# Sheet3_2_AMP.net
KiCad netlist of a schematic drawn in Altium Designer
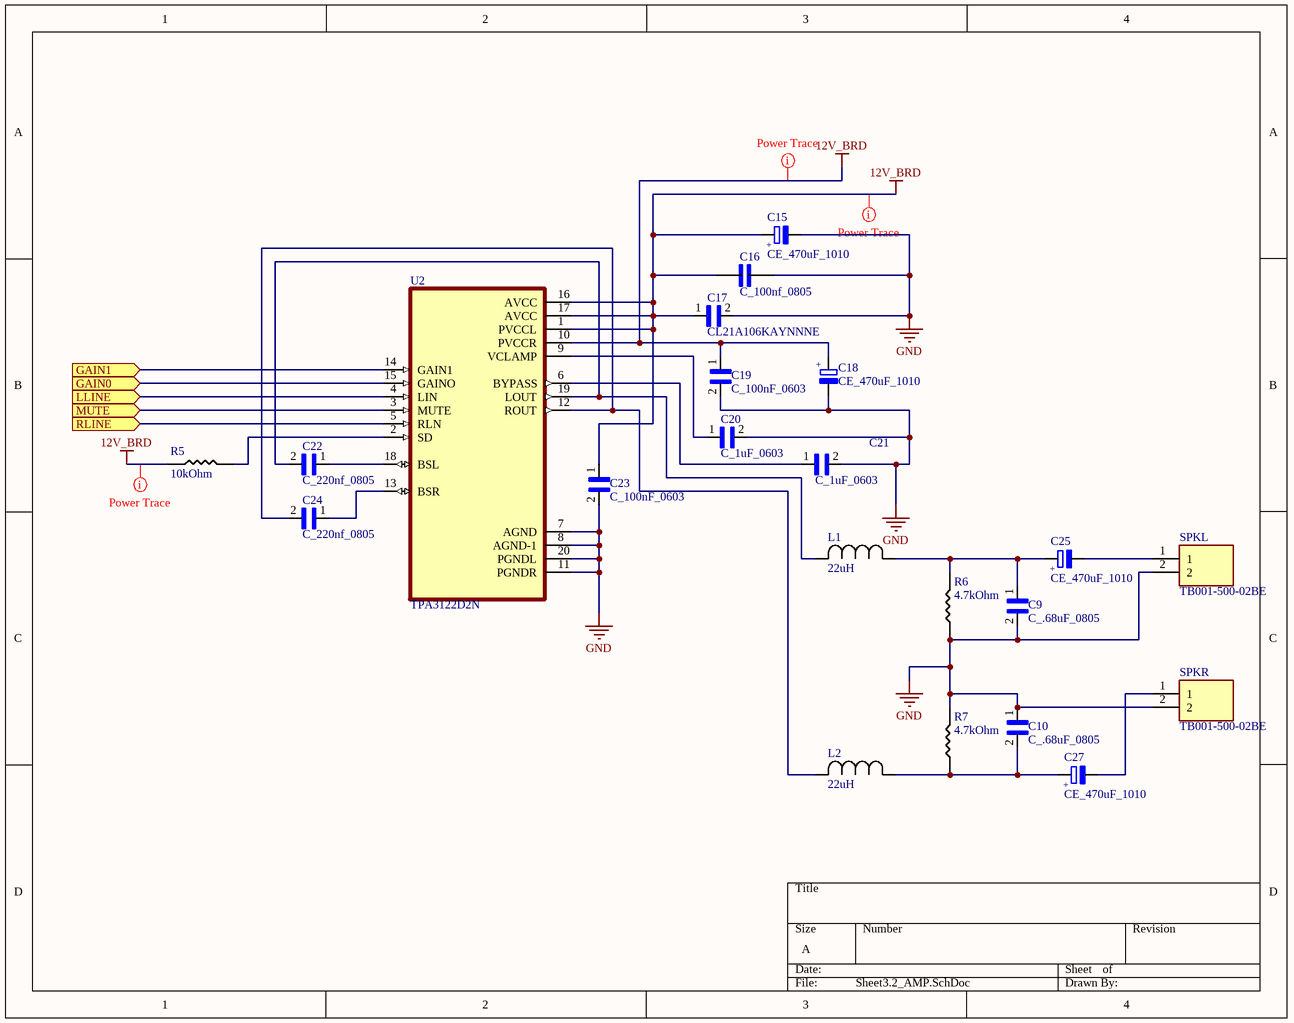
[diagram p0: Sheet3.2_AMP.SchDoc]

(export (version "E")
  (design (tool "Eeschema 10.0.6"))
  (components
    (comp (ref "C9")
      (value "C_.68uF_0805")
      (footprint "CAPC2012X140N")
      (description ".68µF 0805 ±20% 25V Ceramic Capacitor X5R 0805 (2012 Metric)")
      (fields (field (name "MF") "Samsung") (field (name "MP") "CL21B684KOFNNNE"))
      (libsource (lib "Homie_IntegratedLibraryV2") (part "C_.68uF_0805"))
    )
    (comp (ref "C10")
      (value "C_.68uF_0805")
      (footprint "CAPC2012X140N")
      (description ".68µF 0805 ±20% 25V Ceramic Capacitor X5R 0805 (2012 Metric)")
      (fields (field (name "MF") "Samsung") (field (name "MP") "CL21B684KOFNNNE"))
      (libsource (lib "Homie_IntegratedLibraryV2") (part "C_.68uF_0805"))
    )
    (comp (ref "C15")
      (value "CE_470uF_1010")
      (footprint "140CLH-1010")
      (description "Aluminum Electrolytic Capacitors - SMD")
      (fields (field (name "MP") "VZH471M1ETR-1010") (field (name "MF") "Lelon"))
      (libsource (lib "Homie_IntegratedLibraryV2") (part "CE_470uF_1010"))
    )
    (comp (ref "C16")
      (value "C_100nf_0805")
      (footprint "CAPC2012X70")
      (description "0.1ÂµF Â±10% 50V Ceramic Capacitor X7R 0805 _2012 Metric_  CC0805KRX7R9BB104")
      (fields (field (name "MF") "Yageo") (field (name "MP") "CC0805KRX7R9BB104"))
      (libsource (lib "Homie_IntegratedLibraryV2") (part "C_100nf_0805"))
    )
    (comp (ref "C17")
      (value "CL21A106KAYNNNE")
      (footprint "CAPC2012X135N")
      (description "10ÂµF Â±10% 25V Ceramic Capacitor X5R 0805 (2012 Metric)CL21A106KAYNNNE")
      (fields (field (name "MF") "Samsung"))
      (libsource (lib "Homie_IntegratedLibraryV2") (part "CL21A106KAYNNNE"))
    )
    (comp (ref "C18")
      (value "CE_470uF_1010")
      (footprint "140CLH-1010")
      (description "Aluminum Electrolytic Capacitors - SMD")
      (fields (field (name "MP") "VZH471M1ETR-1010") (field (name "MF") "Lelon"))
      (libsource (lib "") (part "CE_470uF_1010_1"))
    )
    (comp (ref "C19")
      (value "C_100nF_0603")
      (footprint "CAPC1608X90")
      (description "0.1礔/100nF  卤10% 50V Ceramic Capacitor X7R 0603 _1608 Metric_")
      (fields (field (name "DIGI-KEY_PART_NUMBER") "311-1344-1-ND") (field (name "MP") "CC0603KRX7R9BB104"))
      (libsource (lib "Homie_IntegratedLibraryV2") (part "C_100nF_0603"))
    )
    (comp (ref "C20")
      (value "C_1uF_0603")
      (footprint "CAPC1608X90N")
      (description "1uF ±10% 50V Ceramic Capacitor X7R 0603 (1608 Metric)")
      (fields (field (name "MP") "CL10A105KB8NNNC") (field (name "MF") "Samsung"))
      (libsource (lib "Homie_IntegratedLibraryV2") (part "C_1uF_0603"))
    )
    (comp (ref "C21")
      (value "C_1uF_0603")
      (footprint "CAPC1608X90N")
      (description "1uF ±10% 50V Ceramic Capacitor X7R 0603 (1608 Metric)")
      (fields (field (name "MP") "CL10A105KB8NNNC") (field (name "MF") "Samsung"))
      (libsource (lib "Homie_IntegratedLibraryV2") (part "C_1uF_0603"))
    )
    (comp (ref "C22")
      (value "C_220nf_0805")
      (footprint "CAPC2012X135N")
      (description "CL21B224KBFNNNE")
      (libsource (lib "Homie_IntegratedLibraryV2") (part "C_220nf_0805"))
    )
    (comp (ref "C23")
      (value "C_100nF_0603")
      (footprint "CAPC1608X90")
      (description "0.1礔/100nF  卤10% 50V Ceramic Capacitor X7R 0603 _1608 Metric_")
      (fields (field (name "DIGI-KEY_PART_NUMBER") "311-1344-1-ND") (field (name "MP") "CC0603KRX7R9BB104"))
      (libsource (lib "Homie_IntegratedLibraryV2") (part "C_100nF_0603"))
    )
    (comp (ref "C24")
      (value "C_220nf_0805")
      (footprint "CAPC2012X135N")
      (description "CL21B224KBFNNNE")
      (libsource (lib "Homie_IntegratedLibraryV2") (part "C_220nf_0805"))
    )
    (comp (ref "C25")
      (value "CE_470uF_1010")
      (footprint "140CLH-1010")
      (description "Aluminum Electrolytic Capacitors - SMD")
      (fields (field (name "MP") "VZH471M1ETR-1010") (field (name "MF") "Lelon"))
      (libsource (lib "Homie_IntegratedLibraryV2") (part "CE_470uF_1010"))
    )
    (comp (ref "C27")
      (value "CE_470uF_1010")
      (footprint "140CLH-1010")
      (description "Aluminum Electrolytic Capacitors - SMD")
      (fields (field (name "MP") "VZH471M1ETR-1010") (field (name "MF") "Lelon"))
      (libsource (lib "Homie_IntegratedLibraryV2") (part "CE_470uF_1010"))
    )
    (comp (ref "L1")
      (value "22uH")
      (footprint "L0805")
      (description "22uH SDFL2012T220KTF")
      (fields (field (name "MANUFACTURER_PART_NUMBER") "SDFL2012T220KTF"))
      (libsource (lib "Homie_IntegratedLibraryV2") (part "L_22uH"))
    )
    (comp (ref "L2")
      (value "22uH")
      (footprint "L0805")
      (description "22uH SDFL2012T220KTF")
      (fields (field (name "MANUFACTURER_PART_NUMBER") "SDFL2012T220KTF"))
      (libsource (lib "Homie_IntegratedLibraryV2") (part "L_22uH"))
    )
    (comp (ref "R5")
      (value "10kOhm")
      (footprint "R0805")
      (description "10kOhm +-1%  0805")
      (fields (field (name "MFR") "Uniroyal") (field (name "Comment") "10 kOhm"))
      (libsource (lib "Homie_IntegratedLibraryV2") (part "R_10kOhm_0805"))
    )
    (comp (ref "R6")
      (value "4.7kOhm")
      (footprint "R0805")
      (description "4.7kOhm +-1%  0805")
      (fields (field (name "MFR") "Uniroyal"))
      (libsource (lib "Homie_IntegratedLibraryV2") (part "R_4.7kOhm_0805"))
    )
    (comp (ref "R7")
      (value "4.7kOhm")
      (footprint "R0805")
      (description "4.7kOhm +-1%  0805")
      (fields (field (name "MFR") "Uniroyal"))
      (libsource (lib "Homie_IntegratedLibraryV2") (part "R_4.7kOhm_0805"))
    )
    (comp (ref "SPKL")
      (value "TB001-500-02BE")
      (footprint "CUI_TB001-500-02BE")
      (description "2~24 Poles, Screw Type, Horizontal, 5.0 Pitch, 22~12 _AWG_, Terminal Block Connector")
      (fields (field (name "MF") "CUI Devices"))
      (libsource (lib "Homie_IntegratedLibraryV3") (part "TB001-500-02BE"))
    )
    (comp (ref "SPKR")
      (value "TB001-500-02BE")
      (footprint "CUI_TB001-500-02BE")
      (description "2~24 Poles, Screw Type, Horizontal, 5.0 Pitch, 22~12 _AWG_, Terminal Block Connector")
      (fields (field (name "MF") "CUI Devices"))
      (libsource (lib "Homie_IntegratedLibraryV3") (part "TB001-500-02BE"))
    )
    (comp (ref "U2")
      (value "TPA3122D2N")
      (footprint "DIP20-2.54-26.2X7.62MM")
      (fields (field (name "MF") "Texas Instruments"))
      (libsource (lib "Homie_IntegratedLibraryV2") (part "TPA3122D2N"))
    )
  )
  (nets
    (net (code "1") (name "/GAIN0") (class "Default")
      (node (ref "U2") (pin "15") (pinfunction "GAINO_15") (pintype "input"))
    )
    (net (code "2") (name "/GAIN1") (class "Default")
      (node (ref "U2") (pin "14") (pinfunction "GAIN1_14") (pintype "input"))
    )
    (net (code "3") (name "/LLINE") (class "Default")
      (node (ref "U2") (pin "4") (pinfunction "LIN_4") (pintype "input"))
    )
    (net (code "4") (name "/MUTE") (class "Default")
      (node (ref "U2") (pin "3") (pinfunction "MUTE_3") (pintype "input"))
    )
    (net (code "5") (name "/RLINE") (class "Default")
      (node (ref "U2") (pin "5") (pinfunction "RLN_5") (pintype "input"))
    )
    (net (code "6") (name "12V_BRD") (class "Default")
      (node (ref "C15") (pin "POS") (pinfunction "POS_POS") (pintype "passive"))
      (node (ref "C16") (pin "1") (pinfunction "1_1") (pintype "passive"))
      (node (ref "C17") (pin "1") (pinfunction "1_1") (pintype "passive"))
      (node (ref "C18") (pin "POS") (pinfunction "POS_POS") (pintype "passive"))
      (node (ref "C19") (pin "1") (pinfunction "1_1") (pintype "passive"))
      (node (ref "C23") (pin "1") (pinfunction "1_1") (pintype "passive"))
      (node (ref "R5") (pin "1") (pinfunction "1_1") (pintype "passive"))
      (node (ref "U2") (pin "1") (pinfunction "PVCCL_1") (pintype "power_in"))
      (node (ref "U2") (pin "10") (pinfunction "PVCCR_10") (pintype "power_in"))
      (node (ref "U2") (pin "16") (pinfunction "AVCC_16") (pintype "power_in"))
      (node (ref "U2") (pin "17") (pinfunction "AVCC_17") (pintype "power_in"))
    )
    (net (code "7") (name "GND") (class "Default")
      (node (ref "C10") (pin "1") (pinfunction "1_1") (pintype "passive"))
      (node (ref "C15") (pin "NEG") (pinfunction "NEG_NEG") (pintype "passive"))
      (node (ref "C16") (pin "2") (pinfunction "2_2") (pintype "passive"))
      (node (ref "C17") (pin "2") (pinfunction "2_2") (pintype "passive"))
      (node (ref "C18") (pin "NEG") (pinfunction "NEG_NEG") (pintype "passive"))
      (node (ref "C19") (pin "2") (pinfunction "2_2") (pintype "passive"))
      (node (ref "C20") (pin "2") (pinfunction "2_2") (pintype "passive"))
      (node (ref "C21") (pin "2") (pinfunction "2_2") (pintype "passive"))
      (node (ref "C23") (pin "2") (pinfunction "2_2") (pintype "passive"))
      (node (ref "C9") (pin "2") (pinfunction "2_2") (pintype "passive"))
      (node (ref "R6") (pin "1") (pinfunction "1_1") (pintype "passive"))
      (node (ref "R7") (pin "2") (pinfunction "2_2") (pintype "passive"))
      (node (ref "SPKL") (pin "2") (pinfunction "2_2") (pintype "passive"))
      (node (ref "SPKR") (pin "2") (pinfunction "2_2") (pintype "passive"))
      (node (ref "U2") (pin "11") (pinfunction "PGNDR_11") (pintype "power_in"))
      (node (ref "U2") (pin "20") (pinfunction "PGNDL_20") (pintype "power_in"))
      (node (ref "U2") (pin "7") (pinfunction "AGND_7") (pintype "power_in"))
      (node (ref "U2") (pin "8") (pinfunction "AGND-1_8") (pintype "power_in"))
    )
    (net (code "8") (name "Net-(C10-Pad2)") (class "Default")
      (node (ref "C10") (pin "2") (pinfunction "2_2") (pintype "passive"))
      (node (ref "C27") (pin "POS") (pinfunction "POS_POS") (pintype "passive"))
      (node (ref "L2") (pin "1") (pinfunction "1_1") (pintype "passive"))
      (node (ref "R7") (pin "1") (pinfunction "1_1") (pintype "passive"))
    )
    (net (code "9") (name "Net-(C25-PadNEG)") (class "Default")
      (node (ref "C25") (pin "NEG") (pinfunction "NEG_NEG") (pintype "passive"))
      (node (ref "SPKL") (pin "1") (pinfunction "1_1") (pintype "passive"))
    )
    (net (code "10") (name "Net-(C25-PadPOS)") (class "Default")
      (node (ref "C25") (pin "POS") (pinfunction "POS_POS") (pintype "passive"))
      (node (ref "C9") (pin "1") (pinfunction "1_1") (pintype "passive"))
      (node (ref "L1") (pin "1") (pinfunction "1_1") (pintype "passive"))
      (node (ref "R6") (pin "2") (pinfunction "2_2") (pintype "passive"))
    )
    (net (code "11") (name "Net-(C27-PadNEG)") (class "Default")
      (node (ref "C27") (pin "NEG") (pinfunction "NEG_NEG") (pintype "passive"))
      (node (ref "SPKR") (pin "1") (pinfunction "1_1") (pintype "passive"))
    )
    (net (code "12") (name "Net-(U2-BSL)") (class "Default")
      (node (ref "C22") (pin "1") (pinfunction "1_1") (pintype "passive"))
      (node (ref "U2") (pin "18") (pinfunction "BSL_18") (pintype "bidirectional"))
    )
    (net (code "13") (name "Net-(U2-BSR)") (class "Default")
      (node (ref "C24") (pin "1") (pinfunction "1_1") (pintype "passive"))
      (node (ref "U2") (pin "13") (pinfunction "BSR_13") (pintype "bidirectional"))
    )
    (net (code "14") (name "Net-(U2-BYPASS)") (class "Default")
      (node (ref "C21") (pin "1") (pinfunction "1_1") (pintype "passive"))
      (node (ref "U2") (pin "6") (pinfunction "BYPASS_6") (pintype "output"))
    )
    (net (code "15") (name "Net-(U2-LOUT)") (class "Default")
      (node (ref "C22") (pin "2") (pinfunction "2_2") (pintype "passive"))
      (node (ref "L1") (pin "2") (pinfunction "2_2") (pintype "passive"))
      (node (ref "U2") (pin "19") (pinfunction "LOUT_19") (pintype "output"))
    )
    (net (code "16") (name "Net-(U2-ROUT)") (class "Default")
      (node (ref "C24") (pin "2") (pinfunction "2_2") (pintype "passive"))
      (node (ref "L2") (pin "2") (pinfunction "2_2") (pintype "passive"))
      (node (ref "U2") (pin "12") (pinfunction "ROUT_12") (pintype "output"))
    )
    (net (code "17") (name "Net-(U2-SD)") (class "Default")
      (node (ref "R5") (pin "2") (pinfunction "2_2") (pintype "passive"))
      (node (ref "U2") (pin "2") (pinfunction "SD_2") (pintype "input"))
    )
    (net (code "18") (name "Net-(U2-VCLAMP)") (class "Default")
      (node (ref "C20") (pin "1") (pinfunction "1_1") (pintype "passive"))
      (node (ref "U2") (pin "9") (pinfunction "VCLAMP_9") (pintype "power_in"))
    )
  )
)
